# SCH_Schematic-Diagram-for-Motion-Control.net
KiCad netlist of a schematic drawn in EasyEDA
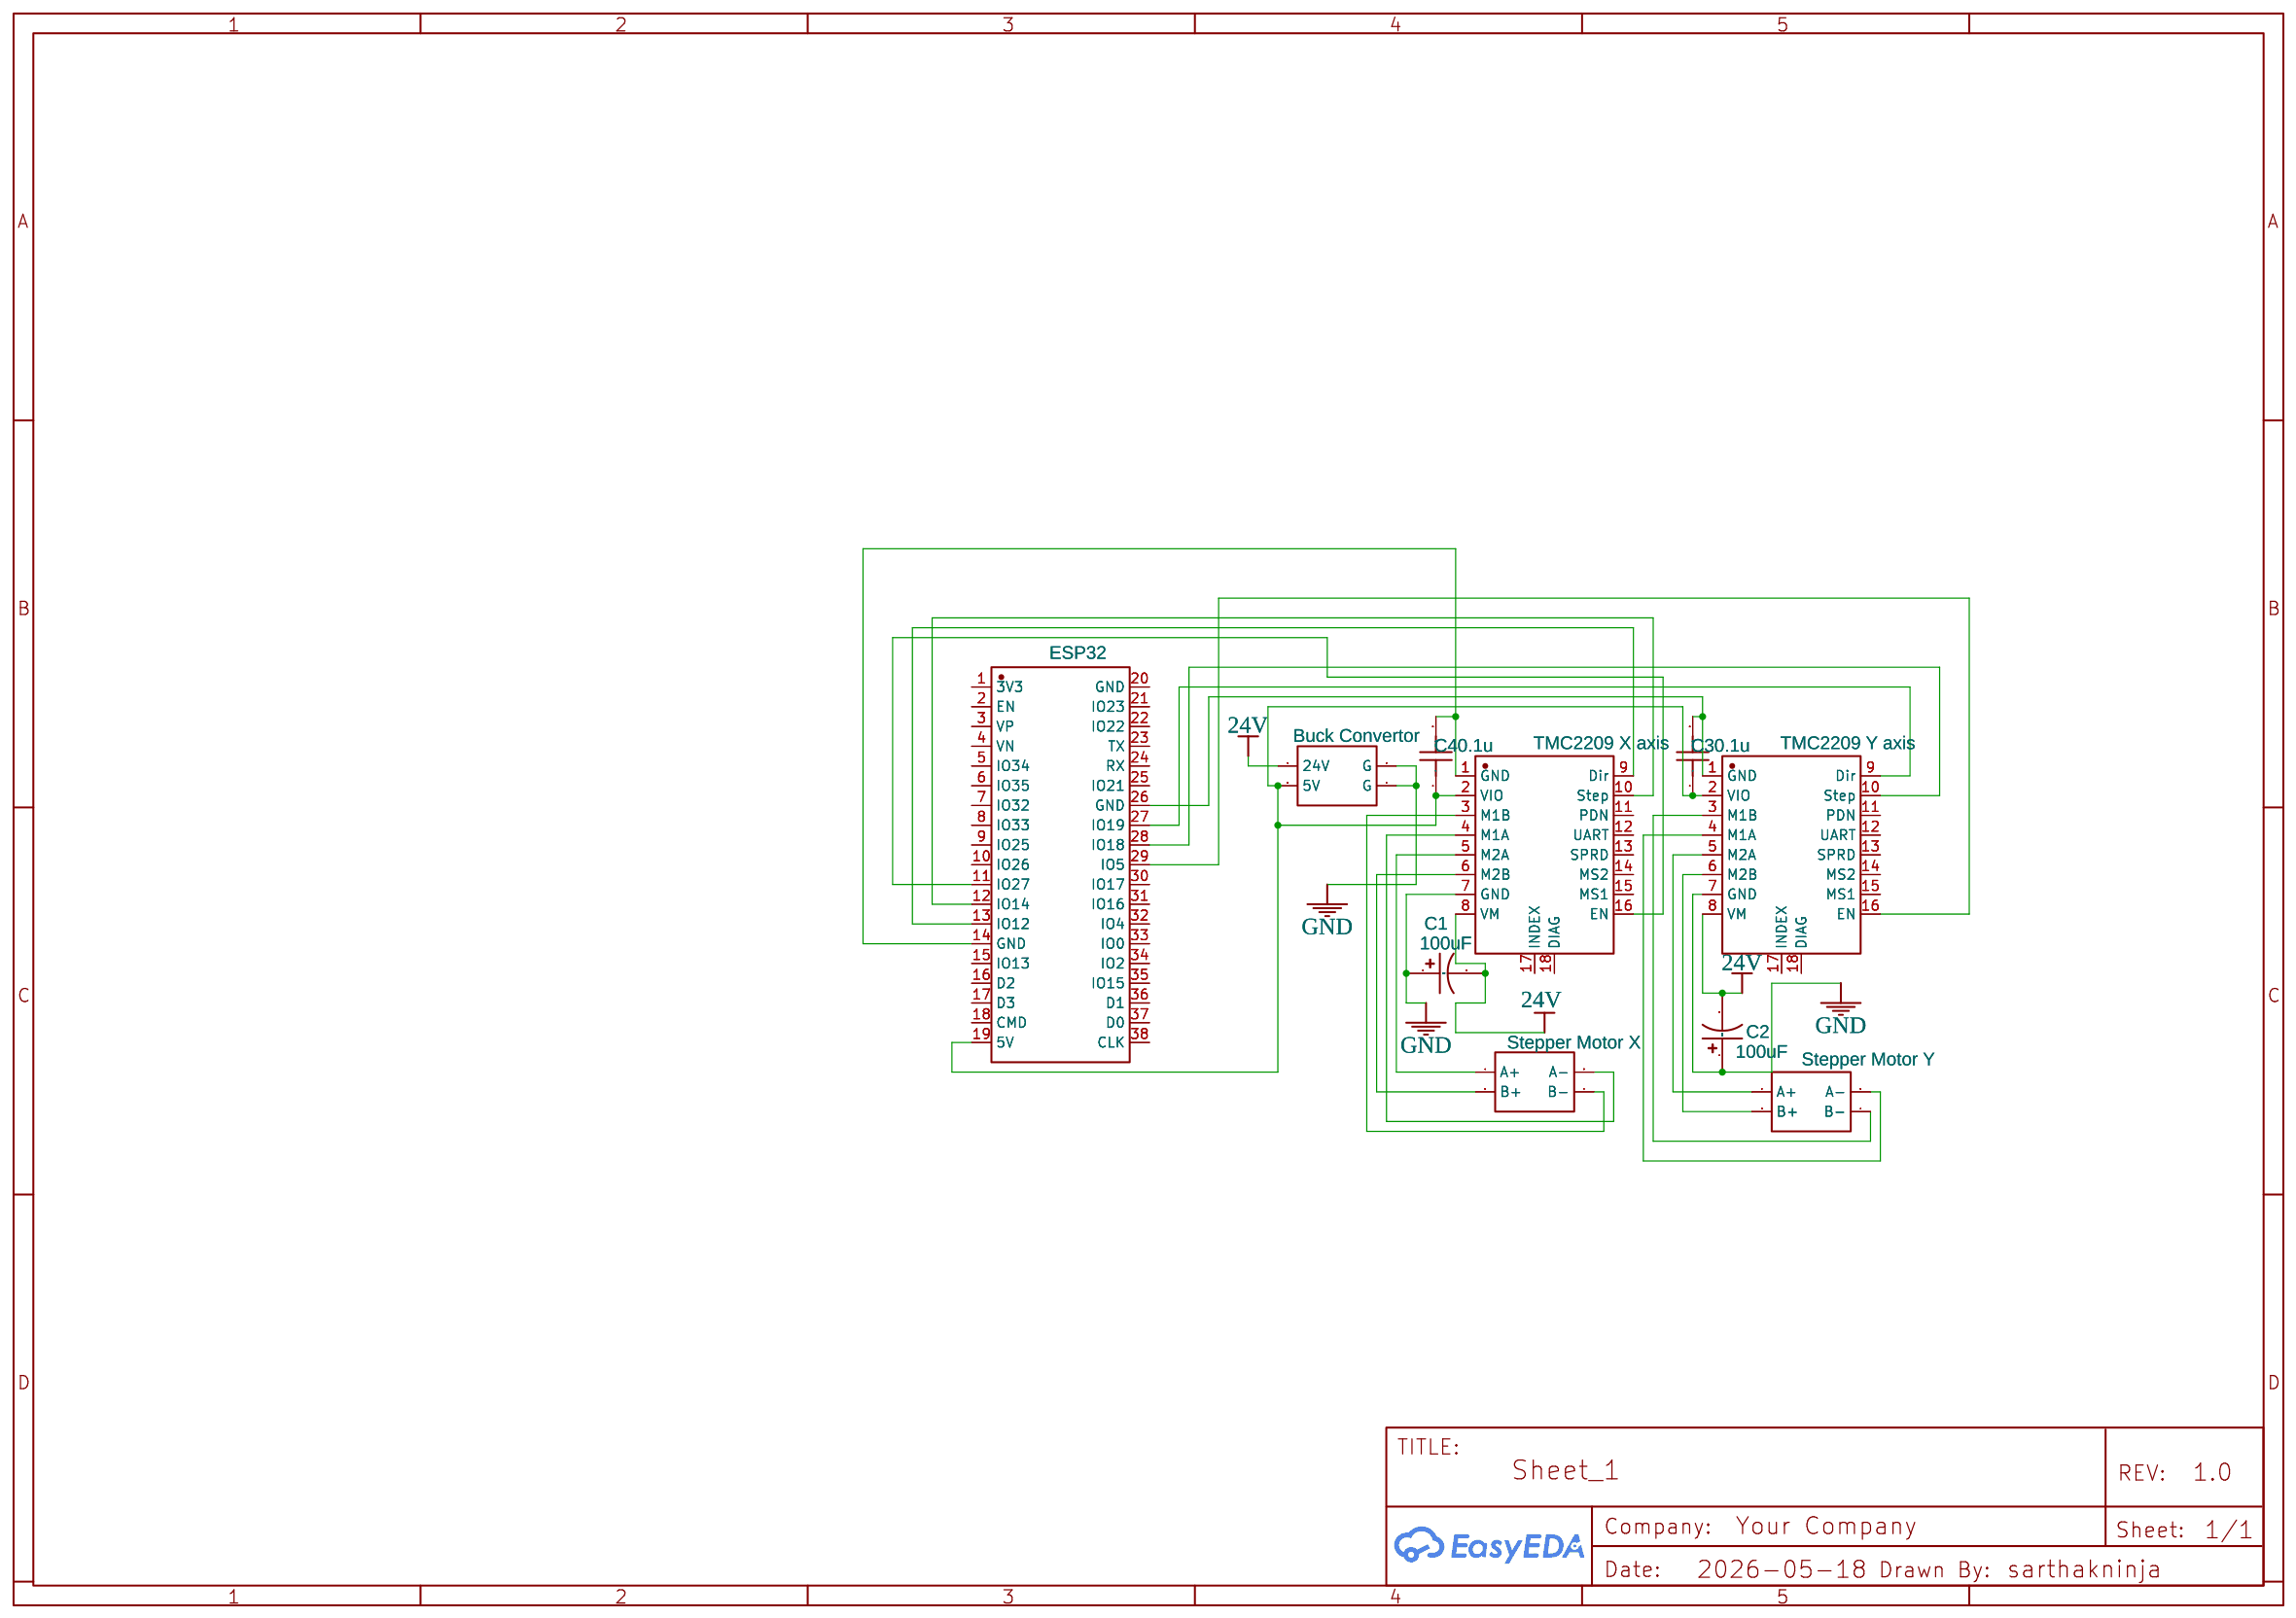
[diagram p0: schematic sheet]

(export (version "E")
  (design (tool "Eeschema 10.0.6"))
  (components
    (comp (ref "C1") (value "100uF") (libsource (lib "") (part "C_Tan_SMD_A_US_1")))
    (comp (ref "C2") (value "100uF") (libsource (lib "") (part "C_Tan_SMD_A_US")))
    (comp (ref "C3") (value "0.1u") (libsource (lib "") (part "C_0603_US")))
    (comp (ref "C4") (value "0.1u") (libsource (lib "") (part "C_0603_US")))
    (comp (ref "J1") (value "Stepper Motor X") (libsource (lib "") (part "HDR-M-2.54_2x2")))
    (comp (ref "J2") (value "Stepper Motor Y") (libsource (lib "") (part "HDR-M-2.54_2x2")))
    (comp (ref "J3") (value "Buck Convertor") (libsource (lib "") (part "HDR-M-2.54_2x2_1")))
    (comp (ref "U1")
      (value "ESP32")
      (fields
        (field (name "Manufacturer Part") "ESP32-DEVKITC-VE")
        (field (name "Manufacturer") "ESPRESSIF(乐鑫)")
      )
      (libsource (lib "") (part "ESP32-DEVKITC-VE"))
    )
    (comp (ref "U2")
      (value "TMC2209 X axis")
      (fields
        (field (name "Manufacturer Part") "TMC2209SILENTSTEPSTICK")
        (field (name "Manufacturer") "TRINAMIC")
      )
      (libsource (lib "") (part "TMC2209SILENTSTEPSTICK"))
    )
    (comp (ref "U3")
      (value "TMC2209 Y axis")
      (fields
        (field (name "Manufacturer Part") "TMC2209SILENTSTEPSTICK")
        (field (name "Manufacturer") "TRINAMIC")
      )
      (libsource (lib "") (part "TMC2209SILENTSTEPSTICK"))
    )
  )
  (nets
    (net (code "1") (name "24V") (class "Default")
      (node (ref "C1") (pin "2") (pinfunction "2_2") (pintype "unspecified"))
      (node (ref "C2") (pin "2") (pinfunction "2_2") (pintype "unspecified"))
      (node (ref "J3") (pin "1") (pinfunction "24V_1") (pintype "input"))
      (node (ref "U2") (pin "8") (pinfunction "VM_8") (pintype "unspecified"))
      (node (ref "U3") (pin "8") (pinfunction "VM_8") (pintype "unspecified"))
    )
    (net (code "2") (name "GND") (class "Default")
      (node (ref "C1") (pin "1") (pinfunction "1_1") (pintype "unspecified"))
      (node (ref "C2") (pin "1") (pinfunction "1_1") (pintype "unspecified"))
      (node (ref "J3") (pin "2") (pinfunction "G_2") (pintype "input"))
      (node (ref "J3") (pin "4") (pinfunction "G_4") (pintype "input"))
      (node (ref "U2") (pin "7") (pinfunction "GND_7") (pintype "unspecified"))
      (node (ref "U3") (pin "7") (pinfunction "GND_7") (pintype "unspecified"))
    )
    (net (code "3") (name "Net-(C3-Pad2)") (class "Default")
      (node (ref "C3") (pin "2") (pinfunction "2_2") (pintype "unspecified"))
      (node (ref "U1") (pin "26") (pinfunction "GND_26") (pintype "unspecified"))
      (node (ref "U3") (pin "1") (pinfunction "GND_1") (pintype "unspecified"))
    )
    (net (code "4") (name "Net-(C4-Pad2)") (class "Default")
      (node (ref "C4") (pin "2") (pinfunction "2_2") (pintype "unspecified"))
      (node (ref "U1") (pin "14") (pinfunction "GND_14") (pintype "unspecified"))
      (node (ref "U2") (pin "1") (pinfunction "GND_1") (pintype "unspecified"))
    )
    (net (code "5") (name "Net-(J1-A+)") (class "Default")
      (node (ref "J1") (pin "1") (pinfunction "A+_1") (pintype "input"))
      (node (ref "U2") (pin "5") (pinfunction "M2A_5") (pintype "unspecified"))
    )
    (net (code "6") (name "Net-(J1-A-)") (class "Default")
      (node (ref "J1") (pin "2") (pinfunction "A-_2") (pintype "input"))
      (node (ref "U2") (pin "4") (pinfunction "M1A_4") (pintype "unspecified"))
    )
    (net (code "7") (name "Net-(J1-B+)") (class "Default")
      (node (ref "J1") (pin "3") (pinfunction "B+_3") (pintype "input"))
      (node (ref "U2") (pin "6") (pinfunction "M2B_6") (pintype "unspecified"))
    )
    (net (code "8") (name "Net-(J1-B-)") (class "Default")
      (node (ref "J1") (pin "4") (pinfunction "B-_4") (pintype "input"))
      (node (ref "U2") (pin "3") (pinfunction "M1B_3") (pintype "unspecified"))
    )
    (net (code "9") (name "Net-(J2-A+)") (class "Default")
      (node (ref "J2") (pin "1") (pinfunction "A+_1") (pintype "input"))
      (node (ref "U3") (pin "5") (pinfunction "M2A_5") (pintype "unspecified"))
    )
    (net (code "10") (name "Net-(J2-A-)") (class "Default")
      (node (ref "J2") (pin "2") (pinfunction "A-_2") (pintype "input"))
      (node (ref "U3") (pin "4") (pinfunction "M1A_4") (pintype "unspecified"))
    )
    (net (code "11") (name "Net-(J2-B+)") (class "Default")
      (node (ref "J2") (pin "3") (pinfunction "B+_3") (pintype "input"))
      (node (ref "U3") (pin "6") (pinfunction "M2B_6") (pintype "unspecified"))
    )
    (net (code "12") (name "Net-(J2-B-)") (class "Default")
      (node (ref "J2") (pin "4") (pinfunction "B-_4") (pintype "input"))
      (node (ref "U3") (pin "3") (pinfunction "M1B_3") (pintype "unspecified"))
    )
    (net (code "13") (name "Net-(J3-5V)") (class "Default")
      (node (ref "C3") (pin "1") (pinfunction "1_1") (pintype "unspecified"))
      (node (ref "C4") (pin "1") (pinfunction "1_1") (pintype "unspecified"))
      (node (ref "J3") (pin "3") (pinfunction "5V_3") (pintype "input"))
      (node (ref "U1") (pin "19") (pinfunction "5V_19") (pintype "unspecified"))
      (node (ref "U2") (pin "2") (pinfunction "VIO_2") (pintype "unspecified"))
      (node (ref "U3") (pin "2") (pinfunction "VIO_2") (pintype "unspecified"))
    )
    (net (code "14") (name "Net-(U1-IO5)") (class "Default")
      (node (ref "U1") (pin "29") (pinfunction "IO5_29") (pintype "unspecified"))
      (node (ref "U3") (pin "16") (pinfunction "EN_16") (pintype "unspecified"))
    )
    (net (code "15") (name "Net-(U1-IO12)") (class "Default")
      (node (ref "U1") (pin "13") (pinfunction "IO12_13") (pintype "unspecified"))
      (node (ref "U2") (pin "9") (pinfunction "Dir_9") (pintype "unspecified"))
    )
    (net (code "16") (name "Net-(U1-IO14)") (class "Default")
      (node (ref "U1") (pin "12") (pinfunction "IO14_12") (pintype "unspecified"))
      (node (ref "U2") (pin "10") (pinfunction "Step_10") (pintype "unspecified"))
    )
    (net (code "17") (name "Net-(U1-IO18)") (class "Default")
      (node (ref "U1") (pin "28") (pinfunction "IO18_28") (pintype "unspecified"))
      (node (ref "U3") (pin "10") (pinfunction "Step_10") (pintype "unspecified"))
    )
    (net (code "18") (name "Net-(U1-IO19)") (class "Default")
      (node (ref "U1") (pin "27") (pinfunction "IO19_27") (pintype "unspecified"))
      (node (ref "U3") (pin "9") (pinfunction "Dir_9") (pintype "unspecified"))
    )
    (net (code "19") (name "Net-(U1-IO27)") (class "Default")
      (node (ref "U1") (pin "11") (pinfunction "IO27_11") (pintype "unspecified"))
      (node (ref "U2") (pin "16") (pinfunction "EN_16") (pintype "unspecified"))
    )
    (net (code "20") (name "unconnected-(U1-3V3-Pad1)") (class "Default")
      (node (ref "U1") (pin "1") (pinfunction "3V3_1") (pintype "unspecified"))
    )
    (net (code "21") (name "unconnected-(U1-CLK-Pad38)") (class "Default")
      (node (ref "U1") (pin "38") (pinfunction "CLK_38") (pintype "unspecified"))
    )
    (net (code "22") (name "unconnected-(U1-CMD-Pad18)") (class "Default")
      (node (ref "U1") (pin "18") (pinfunction "CMD_18") (pintype "unspecified"))
    )
    (net (code "23") (name "unconnected-(U1-D0-Pad37)") (class "Default")
      (node (ref "U1") (pin "37") (pinfunction "D0_37") (pintype "unspecified"))
    )
    (net (code "24") (name "unconnected-(U1-D1-Pad36)") (class "Default")
      (node (ref "U1") (pin "36") (pinfunction "D1_36") (pintype "unspecified"))
    )
    (net (code "25") (name "unconnected-(U1-D2-Pad16)") (class "Default")
      (node (ref "U1") (pin "16") (pinfunction "D2_16") (pintype "unspecified"))
    )
    (net (code "26") (name "unconnected-(U1-D3-Pad17)") (class "Default")
      (node (ref "U1") (pin "17") (pinfunction "D3_17") (pintype "unspecified"))
    )
    (net (code "27") (name "unconnected-(U1-EN-Pad2)") (class "Default")
      (node (ref "U1") (pin "2") (pinfunction "EN_2") (pintype "unspecified"))
    )
    (net (code "28") (name "unconnected-(U1-GND-Pad20)") (class "Default")
      (node (ref "U1") (pin "20") (pinfunction "GND_20") (pintype "unspecified"))
    )
    (net (code "29") (name "unconnected-(U1-IO0-Pad33)") (class "Default")
      (node (ref "U1") (pin "33") (pinfunction "IO0_33") (pintype "unspecified"))
    )
    (net (code "30") (name "unconnected-(U1-IO2-Pad34)") (class "Default")
      (node (ref "U1") (pin "34") (pinfunction "IO2_34") (pintype "unspecified"))
    )
    (net (code "31") (name "unconnected-(U1-IO4-Pad32)") (class "Default")
      (node (ref "U1") (pin "32") (pinfunction "IO4_32") (pintype "unspecified"))
    )
    (net (code "32") (name "unconnected-(U1-IO13-Pad15)") (class "Default")
      (node (ref "U1") (pin "15") (pinfunction "IO13_15") (pintype "unspecified"))
    )
    (net (code "33") (name "unconnected-(U1-IO15-Pad35)") (class "Default")
      (node (ref "U1") (pin "35") (pinfunction "IO15_35") (pintype "unspecified"))
    )
    (net (code "34") (name "unconnected-(U1-IO16-Pad31)") (class "Default")
      (node (ref "U1") (pin "31") (pinfunction "IO16_31") (pintype "unspecified"))
    )
    (net (code "35") (name "unconnected-(U1-IO17-Pad30)") (class "Default")
      (node (ref "U1") (pin "30") (pinfunction "IO17_30") (pintype "unspecified"))
    )
    (net (code "36") (name "unconnected-(U1-IO21-Pad25)") (class "Default")
      (node (ref "U1") (pin "25") (pinfunction "IO21_25") (pintype "unspecified"))
    )
    (net (code "37") (name "unconnected-(U1-IO22-Pad22)") (class "Default")
      (node (ref "U1") (pin "22") (pinfunction "IO22_22") (pintype "unspecified"))
    )
    (net (code "38") (name "unconnected-(U1-IO23-Pad21)") (class "Default")
      (node (ref "U1") (pin "21") (pinfunction "IO23_21") (pintype "unspecified"))
    )
    (net (code "39") (name "unconnected-(U1-IO25-Pad9)") (class "Default")
      (node (ref "U1") (pin "9") (pinfunction "IO25_9") (pintype "unspecified"))
    )
    (net (code "40") (name "unconnected-(U1-IO26-Pad10)") (class "Default")
      (node (ref "U1") (pin "10") (pinfunction "IO26_10") (pintype "unspecified"))
    )
    (net (code "41") (name "unconnected-(U1-IO32-Pad7)") (class "Default")
      (node (ref "U1") (pin "7") (pinfunction "IO32_7") (pintype "unspecified"))
    )
    (net (code "42") (name "unconnected-(U1-IO33-Pad8)") (class "Default")
      (node (ref "U1") (pin "8") (pinfunction "IO33_8") (pintype "unspecified"))
    )
    (net (code "43") (name "unconnected-(U1-IO34-Pad5)") (class "Default")
      (node (ref "U1") (pin "5") (pinfunction "IO34_5") (pintype "unspecified"))
    )
    (net (code "44") (name "unconnected-(U1-IO35-Pad6)") (class "Default")
      (node (ref "U1") (pin "6") (pinfunction "IO35_6") (pintype "unspecified"))
    )
    (net (code "45") (name "unconnected-(U1-RX-Pad24)") (class "Default")
      (node (ref "U1") (pin "24") (pinfunction "RX_24") (pintype "unspecified"))
    )
    (net (code "46") (name "unconnected-(U1-TX-Pad23)") (class "Default")
      (node (ref "U1") (pin "23") (pinfunction "TX_23") (pintype "unspecified"))
    )
    (net (code "47") (name "unconnected-(U1-VN-Pad4)") (class "Default")
      (node (ref "U1") (pin "4") (pinfunction "VN_4") (pintype "unspecified"))
    )
    (net (code "48") (name "unconnected-(U1-VP-Pad3)") (class "Default")
      (node (ref "U1") (pin "3") (pinfunction "VP_3") (pintype "unspecified"))
    )
    (net (code "49") (name "unconnected-(U2-DIAG-Pad18)") (class "Default")
      (node (ref "U2") (pin "18") (pinfunction "DIAG_18") (pintype "unspecified"))
    )
    (net (code "50") (name "unconnected-(U2-INDEX-Pad17)") (class "Default")
      (node (ref "U2") (pin "17") (pinfunction "INDEX_17") (pintype "unspecified"))
    )
    (net (code "51") (name "unconnected-(U2-MS1-Pad15)") (class "Default")
      (node (ref "U2") (pin "15") (pinfunction "MS1_15") (pintype "unspecified"))
    )
    (net (code "52") (name "unconnected-(U2-MS2-Pad14)") (class "Default")
      (node (ref "U2") (pin "14") (pinfunction "MS2_14") (pintype "unspecified"))
    )
    (net (code "53") (name "unconnected-(U2-PDN-Pad11)") (class "Default")
      (node (ref "U2") (pin "11") (pinfunction "PDN_11") (pintype "unspecified"))
    )
    (net (code "54") (name "unconnected-(U2-SPRD-Pad13)") (class "Default")
      (node (ref "U2") (pin "13") (pinfunction "SPRD_13") (pintype "unspecified"))
    )
    (net (code "55") (name "unconnected-(U2-UART-Pad12)") (class "Default")
      (node (ref "U2") (pin "12") (pinfunction "UART_12") (pintype "unspecified"))
    )
    (net (code "56") (name "unconnected-(U3-DIAG-Pad18)") (class "Default")
      (node (ref "U3") (pin "18") (pinfunction "DIAG_18") (pintype "unspecified"))
    )
    (net (code "57") (name "unconnected-(U3-INDEX-Pad17)") (class "Default")
      (node (ref "U3") (pin "17") (pinfunction "INDEX_17") (pintype "unspecified"))
    )
    (net (code "58") (name "unconnected-(U3-MS1-Pad15)") (class "Default")
      (node (ref "U3") (pin "15") (pinfunction "MS1_15") (pintype "unspecified"))
    )
    (net (code "59") (name "unconnected-(U3-MS2-Pad14)") (class "Default")
      (node (ref "U3") (pin "14") (pinfunction "MS2_14") (pintype "unspecified"))
    )
    (net (code "60") (name "unconnected-(U3-PDN-Pad11)") (class "Default")
      (node (ref "U3") (pin "11") (pinfunction "PDN_11") (pintype "unspecified"))
    )
    (net (code "61") (name "unconnected-(U3-SPRD-Pad13)") (class "Default")
      (node (ref "U3") (pin "13") (pinfunction "SPRD_13") (pintype "unspecified"))
    )
    (net (code "62") (name "unconnected-(U3-UART-Pad12)") (class "Default")
      (node (ref "U3") (pin "12") (pinfunction "UART_12") (pintype "unspecified"))
    )
  )
)
